# Adafruit_BNO055_STEMMA_QT.net
KiCad netlist of a schematic drawn in EAGLE
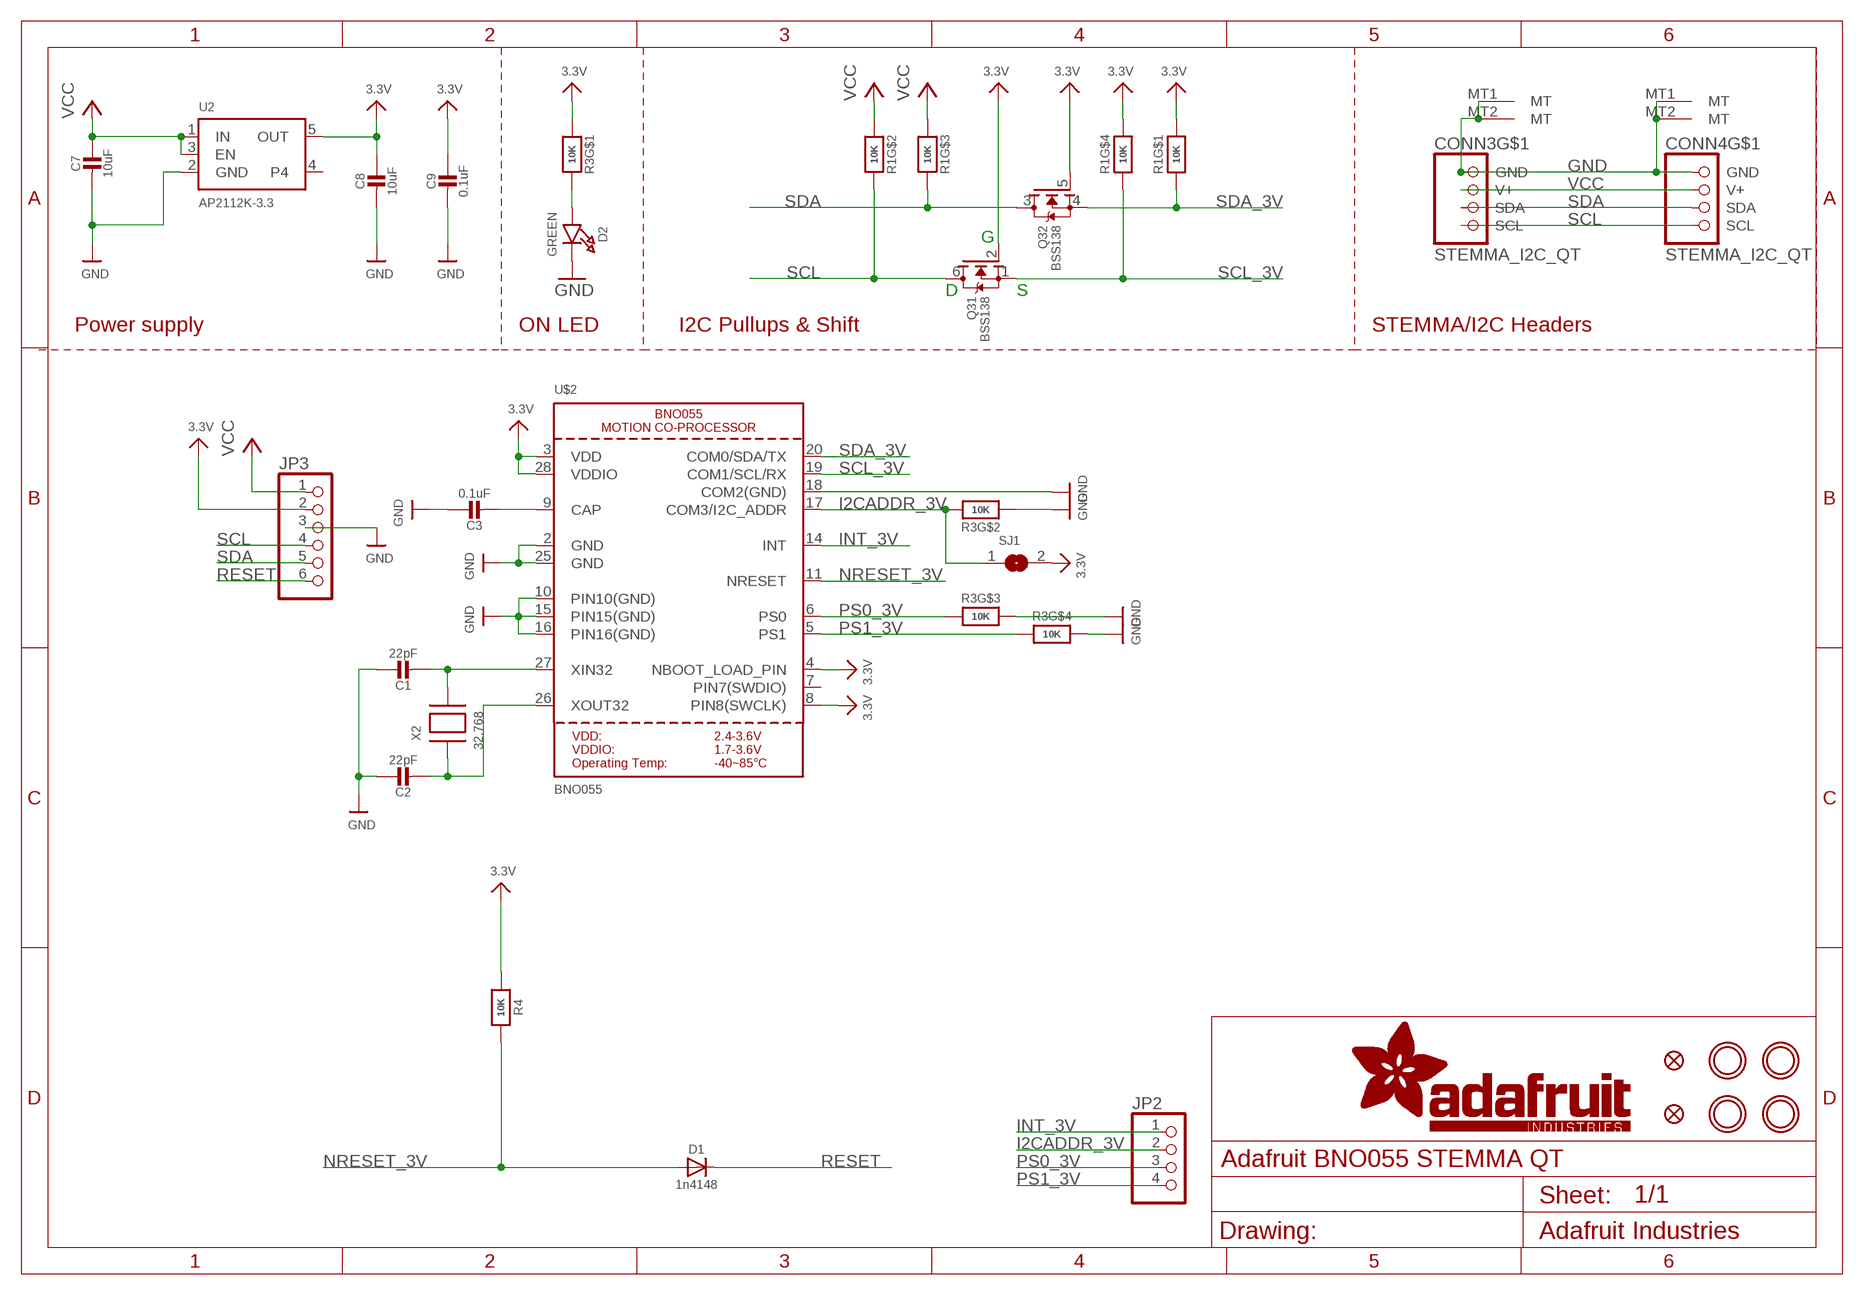
[diagram p0: schematic, sheet 1]

(export (version "E")
  (design (tool "Eeschema 10.0.6"))
  (components
    (comp (ref "C1")
      (value "22pF")
      (footprint "eagle-import:0603-NO")
      (libsource (lib "eagle-import") (part "CAP_CERAMIC0603_NO"))
    )
    (comp (ref "C2")
      (value "22pF")
      (footprint "eagle-import:0603-NO")
      (libsource (lib "eagle-import") (part "CAP_CERAMIC0603_NO"))
    )
    (comp (ref "C3")
      (value "0.1uF")
      (footprint "eagle-import:0603-NO")
      (libsource (lib "eagle-import") (part "CAP_CERAMIC0603_NO"))
    )
    (comp (ref "C7")
      (value "10uF")
      (footprint "eagle-import:0805-NO")
      (libsource (lib "eagle-import") (part "CAP_CERAMIC0805-NOOUTLINE"))
    )
    (comp (ref "C8")
      (value "10uF")
      (footprint "eagle-import:0805-NO")
      (libsource (lib "eagle-import") (part "CAP_CERAMIC0805-NOOUTLINE"))
    )
    (comp (ref "C9")
      (value "0.1uF")
      (footprint "eagle-import:0603-NO")
      (libsource (lib "eagle-import") (part "CAP_CERAMIC0603_NO"))
    )
    (comp (ref "CONN3")
      (value "STEMMA_I2C_QT")
      (footprint "eagle-import:JST_SH4")
      (libsource (lib "eagle-import") (part "STEMMA_I2C_QT"))
    )
    (comp (ref "CONN4")
      (value "STEMMA_I2C_QT")
      (footprint "eagle-import:JST_SH4")
      (libsource (lib "eagle-import") (part "STEMMA_I2C_QT"))
    )
    (comp (ref "D1")
      (value "1n4148")
      (footprint "eagle-import:SOD-323")
      (libsource (lib "eagle-import") (part "DIODESOD-323"))
    )
    (comp (ref "D2")
      (value "GREEN")
      (footprint "eagle-import:CHIPLED_0603_NOOUTLINE")
      (libsource (lib "eagle-import") (part "LED0603_NOOUTLINE"))
    )
    (comp (ref "FID3")
      (value "FIDUCIAL_1MM")
      (footprint "eagle-import:FIDUCIAL_1MM")
      (libsource (lib "eagle-import") (part "FIDUCIAL_1MM"))
    )
    (comp (ref "FID4")
      (value "FIDUCIAL_1MM")
      (footprint "eagle-import:FIDUCIAL_1MM")
      (libsource (lib "eagle-import") (part "FIDUCIAL_1MM"))
    )
    (comp (ref "JP2")
      (value "HEADER-1X476MIL")
      (footprint "eagle-import:1X04_ROUND_76")
      (libsource (lib "eagle-import") (part "HEADER-1X476MIL"))
    )
    (comp (ref "JP3")
      (value "HEADER-1X670MIL")
      (footprint "eagle-import:1X06_ROUND_70")
      (libsource (lib "eagle-import") (part "HEADER-1X670MIL"))
    )
    (comp (ref "Q3")
      (value "BSS138")
      (footprint "eagle-import:SOT363")
      (libsource (lib "eagle-import") (part "MOSFET-N_DUAL"))
    )
    (comp (ref "R1")
      (value "10K")
      (footprint "eagle-import:RESPACK_4X0603")
      (libsource (lib "eagle-import") (part "RESISTOR_4PACK"))
    )
    (comp (ref "R3")
      (value "10K")
      (footprint "eagle-import:RESPACK_4X0603")
      (libsource (lib "eagle-import") (part "RESISTOR_4PACK"))
    )
    (comp (ref "R4")
      (value "10K")
      (footprint "eagle-import:0603-NO")
      (libsource (lib "eagle-import") (part "RESISTOR_0603_NOOUT"))
    )
    (comp (ref "SJ1")
      (value "SOLDERJUMPER")
      (footprint "eagle-import:SOLDERJUMPER_ARROW_NOPASTE")
      (libsource (lib "eagle-import") (part "SOLDERJUMPER"))
    )
    (comp (ref "U$2")
      (value "BNO055")
      (footprint "eagle-import:BNO055")
      (libsource (lib "eagle-import") (part "BNO055"))
    )
    (comp (ref "U$45")
      (value "MOUNTINGHOLE2.5")
      (footprint "eagle-import:MOUNTINGHOLE_2.5_PLATED")
      (libsource (lib "eagle-import") (part "MOUNTINGHOLE2.5"))
    )
    (comp (ref "U$46")
      (value "MOUNTINGHOLE2.5")
      (footprint "eagle-import:MOUNTINGHOLE_2.5_PLATED")
      (libsource (lib "eagle-import") (part "MOUNTINGHOLE2.5"))
    )
    (comp (ref "U$48")
      (value "MOUNTINGHOLE2.5")
      (footprint "eagle-import:MOUNTINGHOLE_2.5_PLATED")
      (libsource (lib "eagle-import") (part "MOUNTINGHOLE2.5"))
    )
    (comp (ref "U$49")
      (value "MOUNTINGHOLE2.5")
      (footprint "eagle-import:MOUNTINGHOLE_2.5_PLATED")
      (libsource (lib "eagle-import") (part "MOUNTINGHOLE2.5"))
    )
    (comp (ref "U2")
      (value "AP2112K-3.3")
      (footprint "eagle-import:SOT23-5")
      (libsource (lib "eagle-import") (part "VREG_SOT23-5"))
    )
    (comp (ref "X2")
      (value "32.768")
      (footprint "eagle-import:XTAL3215")
      (libsource (lib "eagle-import") (part "XTAL-3.2X1.5"))
    )
  )
  (nets
    (net (code "1") (name "/I2CADDR_3V") (class "Default")
      (node (ref "JP2") (pin "2") (pinfunction "2_2") (pintype "passive"))
      (node (ref "R3") (pin "7") (pinfunction "2_7") (pintype "passive"))
      (node (ref "SJ1") (pin "1") (pinfunction "1_1") (pintype "passive"))
      (node (ref "U$2") (pin "17") (pinfunction "COM3/I2C_ADDR_17") (pintype "bidirectional"))
    )
    (net (code "2") (name "/INT_3V") (class "Default")
      (node (ref "JP2") (pin "1") (pinfunction "1_1") (pintype "passive"))
      (node (ref "U$2") (pin "14") (pinfunction "INT_14") (pintype "output"))
    )
    (net (code "3") (name "/NRESET_3V") (class "Default")
      (node (ref "D1") (pin "A") (pinfunction "A_A") (pintype "passive"))
      (node (ref "R4") (pin "2") (pinfunction "2_2") (pintype "passive"))
      (node (ref "U$2") (pin "11") (pinfunction "NRESET_11") (pintype "bidirectional"))
    )
    (net (code "4") (name "/PS0_3V") (class "Default")
      (node (ref "JP2") (pin "3") (pinfunction "3_3") (pintype "passive"))
      (node (ref "R3") (pin "3") (pinfunction "1_3") (pintype "passive"))
      (node (ref "U$2") (pin "6") (pinfunction "PS0_6") (pintype "input"))
    )
    (net (code "5") (name "/PS1_3V") (class "Default")
      (node (ref "JP2") (pin "4") (pinfunction "4_4") (pintype "passive"))
      (node (ref "R3") (pin "4") (pinfunction "1_4") (pintype "passive"))
      (node (ref "U$2") (pin "5") (pinfunction "PS1_5") (pintype "input"))
    )
    (net (code "6") (name "/RESET") (class "Default")
      (node (ref "D1") (pin "C") (pinfunction "C_C") (pintype "passive"))
      (node (ref "JP3") (pin "6") (pinfunction "6_6") (pintype "passive"))
    )
    (net (code "7") (name "/SCL") (class "Default")
      (node (ref "CONN3") (pin "4") (pinfunction "SCL_4") (pintype "passive"))
      (node (ref "CONN4") (pin "4") (pinfunction "SCL_4") (pintype "passive"))
      (node (ref "JP3") (pin "4") (pinfunction "4_4") (pintype "passive"))
      (node (ref "Q3") (pin "6") (pinfunction "D_6") (pintype "bidirectional"))
      (node (ref "R1") (pin "7") (pinfunction "2_7") (pintype "passive"))
    )
    (net (code "8") (name "/SCL_3V") (class "Default")
      (node (ref "Q3") (pin "1") (pinfunction "S_1") (pintype "bidirectional"))
      (node (ref "R1") (pin "5") (pinfunction "2_5") (pintype "passive"))
      (node (ref "U$2") (pin "19") (pinfunction "COM1/SCL/RX_19") (pintype "bidirectional"))
    )
    (net (code "9") (name "/SDA") (class "Default")
      (node (ref "CONN3") (pin "3") (pinfunction "SDA_3") (pintype "passive"))
      (node (ref "CONN4") (pin "3") (pinfunction "SDA_3") (pintype "passive"))
      (node (ref "JP3") (pin "5") (pinfunction "5_5") (pintype "passive"))
      (node (ref "Q3") (pin "3") (pinfunction "D_3") (pintype "bidirectional"))
      (node (ref "R1") (pin "6") (pinfunction "2_6") (pintype "passive"))
    )
    (net (code "10") (name "/SDA_3V") (class "Default")
      (node (ref "Q3") (pin "4") (pinfunction "S_4") (pintype "bidirectional"))
      (node (ref "R1") (pin "8") (pinfunction "2_8") (pintype "passive"))
      (node (ref "U$2") (pin "20") (pinfunction "COM0/SDA/TX_20") (pintype "bidirectional"))
    )
    (net (code "11") (name "3.3V") (class "Default")
      (node (ref "C8") (pin "1") (pinfunction "1_1") (pintype "passive"))
      (node (ref "C9") (pin "1") (pinfunction "1_1") (pintype "passive"))
      (node (ref "JP3") (pin "2") (pinfunction "2_2") (pintype "passive"))
      (node (ref "Q3") (pin "2") (pinfunction "G_2") (pintype "bidirectional"))
      (node (ref "Q3") (pin "5") (pinfunction "G_5") (pintype "bidirectional"))
      (node (ref "R1") (pin "1") (pinfunction "1_1") (pintype "passive"))
      (node (ref "R1") (pin "4") (pinfunction "1_4") (pintype "passive"))
      (node (ref "R3") (pin "1") (pinfunction "1_1") (pintype "passive"))
      (node (ref "R4") (pin "1") (pinfunction "1_1") (pintype "passive"))
      (node (ref "SJ1") (pin "2") (pinfunction "2_2") (pintype "passive"))
      (node (ref "U$2") (pin "28") (pinfunction "VDDIO_28") (pintype "power_in"))
      (node (ref "U$2") (pin "3") (pinfunction "VDD_3") (pintype "power_in"))
      (node (ref "U$2") (pin "4") (pinfunction "NBOOT_LOAD_PIN_4") (pintype "bidirectional"))
      (node (ref "U$2") (pin "8") (pinfunction "PIN8(SWCLK)_8") (pintype "bidirectional"))
      (node (ref "U2") (pin "5") (pinfunction "OUT_5") (pintype "power_in"))
    )
    (net (code "12") (name "GND") (class "Default")
      (node (ref "C1") (pin "1") (pinfunction "1_1") (pintype "passive"))
      (node (ref "C2") (pin "1") (pinfunction "1_1") (pintype "passive"))
      (node (ref "C3") (pin "1") (pinfunction "1_1") (pintype "passive"))
      (node (ref "C7") (pin "2") (pinfunction "2_2") (pintype "passive"))
      (node (ref "C8") (pin "2") (pinfunction "2_2") (pintype "passive"))
      (node (ref "C9") (pin "2") (pinfunction "2_2") (pintype "passive"))
      (node (ref "CONN3") (pin "1") (pinfunction "GND_1") (pintype "passive"))
      (node (ref "CONN3") (pin "MT1") (pinfunction "MT_MT1") (pintype "bidirectional"))
      (node (ref "CONN3") (pin "MT2") (pinfunction "MT_MT2") (pintype "bidirectional"))
      (node (ref "CONN4") (pin "1") (pinfunction "GND_1") (pintype "passive"))
      (node (ref "CONN4") (pin "MT1") (pinfunction "MT_MT1") (pintype "bidirectional"))
      (node (ref "CONN4") (pin "MT2") (pinfunction "MT_MT2") (pintype "bidirectional"))
      (node (ref "D2") (pin "C") (pinfunction "C_C") (pintype "passive"))
      (node (ref "JP3") (pin "3") (pinfunction "3_3") (pintype "passive"))
      (node (ref "R3") (pin "2") (pinfunction "1_2") (pintype "passive"))
      (node (ref "R3") (pin "5") (pinfunction "2_5") (pintype "passive"))
      (node (ref "R3") (pin "6") (pinfunction "2_6") (pintype "passive"))
      (node (ref "U$2") (pin "10") (pinfunction "PIN10(GND)_10") (pintype "bidirectional"))
      (node (ref "U$2") (pin "15") (pinfunction "PIN15(GND)_15") (pintype "bidirectional"))
      (node (ref "U$2") (pin "16") (pinfunction "PIN16(GND)_16") (pintype "bidirectional"))
      (node (ref "U$2") (pin "18") (pinfunction "COM2(GND)_18") (pintype "bidirectional"))
      (node (ref "U$2") (pin "2") (pinfunction "GND_2") (pintype "power_in"))
      (node (ref "U$2") (pin "25") (pinfunction "GND_25") (pintype "power_in"))
      (node (ref "U2") (pin "2") (pinfunction "GND_2") (pintype "power_in"))
    )
    (net (code "13") (name "Net-(R3A-2)") (class "Default")
      (node (ref "D2") (pin "A") (pinfunction "A_A") (pintype "passive"))
      (node (ref "R3") (pin "8") (pinfunction "2_8") (pintype "passive"))
    )
    (net (code "14") (name "Net-(U$2-CAP)") (class "Default")
      (node (ref "C3") (pin "2") (pinfunction "2_2") (pintype "passive"))
      (node (ref "U$2") (pin "9") (pinfunction "CAP_9") (pintype "passive"))
    )
    (net (code "15") (name "Net-(U$2-XIN32)") (class "Default")
      (node (ref "C1") (pin "2") (pinfunction "2_2") (pintype "passive"))
      (node (ref "U$2") (pin "27") (pinfunction "XIN32_27") (pintype "input"))
      (node (ref "X2") (pin "P$2") (pinfunction "P$2_P$2") (pintype "bidirectional"))
    )
    (net (code "16") (name "Net-(U$2-XOUT32)") (class "Default")
      (node (ref "C2") (pin "2") (pinfunction "2_2") (pintype "passive"))
      (node (ref "U$2") (pin "26") (pinfunction "XOUT32_26") (pintype "output"))
      (node (ref "X2") (pin "P$1") (pinfunction "P$1_P$1") (pintype "bidirectional"))
    )
    (net (code "17") (name "VCC") (class "Default")
      (node (ref "C7") (pin "1") (pinfunction "1_1") (pintype "passive"))
      (node (ref "CONN3") (pin "2") (pinfunction "V+_2") (pintype "passive"))
      (node (ref "CONN4") (pin "2") (pinfunction "V+_2") (pintype "passive"))
      (node (ref "JP3") (pin "1") (pinfunction "1_1") (pintype "passive"))
      (node (ref "R1") (pin "2") (pinfunction "1_2") (pintype "passive"))
      (node (ref "R1") (pin "3") (pinfunction "1_3") (pintype "passive"))
      (node (ref "U2") (pin "1") (pinfunction "IN_1") (pintype "power_in"))
      (node (ref "U2") (pin "3") (pinfunction "EN_3") (pintype "input"))
    )
    (net (code "18") (name "unconnected-(U$2-PIN7(SWDIO)-Pad7)") (class "Default")
      (node (ref "U$2") (pin "7") (pinfunction "PIN7(SWDIO)_7") (pintype "bidirectional"))
    )
    (net (code "19") (name "unconnected-(U2-P4-Pad4)") (class "Default")
      (node (ref "U2") (pin "4") (pinfunction "P4_4") (pintype "bidirectional"))
    )
  )
)
